# gerbalino0_3_1.net
KiCad netlist of a schematic drawn in EAGLE
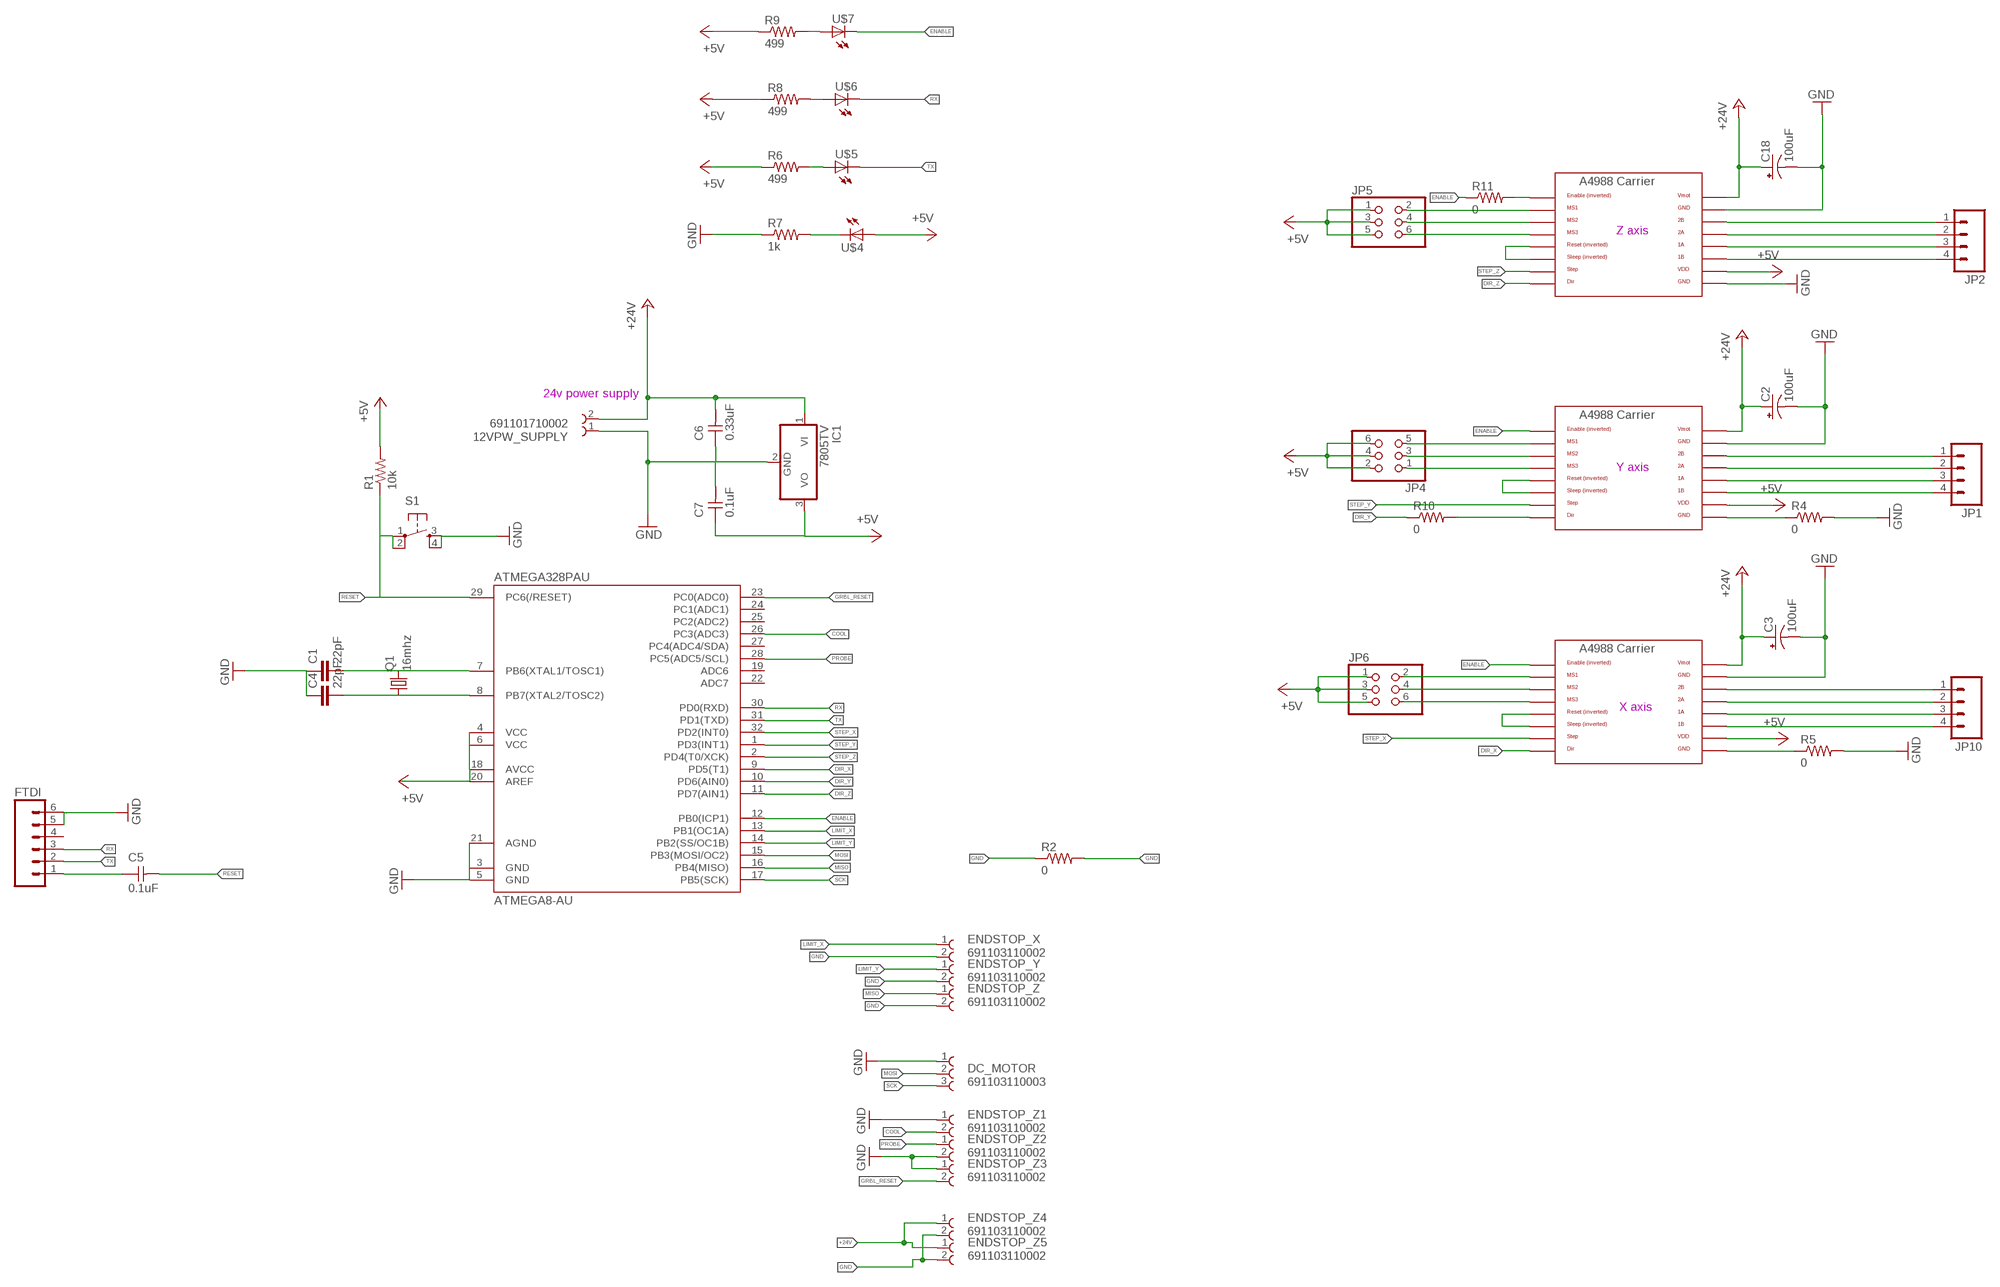
[diagram p0: schematic, sheet 1]

(export (version "E")
  (design (tool "Eeschema 10.0.6"))
  (components
    (comp (ref "12VPW_SUPPLY")
      (value "691101710002")
      (footprint "eagle-import:691101710002")
      (libsource (lib "eagle-import") (part "691101710002"))
    )
    (comp (ref "ATMEGA328PAU")
      (value "ATMEGA8-AU")
      (footprint "eagle-import:TQFP32-08")
      (libsource (lib "eagle-import") (part "ATMEGA8-AU"))
    )
    (comp (ref "C1")
      (value "22pF")
      (footprint "eagle-import:1206")
      (libsource (lib "eagle-import") (part "CAP1206"))
    )
    (comp (ref "C2")
      (value "100uF")
      (footprint "eagle-import:UD-10X10_NICHICON")
      (libsource (lib "eagle-import") (part "CPOL-USUD-10X10"))
    )
    (comp (ref "C3")
      (value "100uF")
      (footprint "eagle-import:UD-10X10_NICHICON")
      (libsource (lib "eagle-import") (part "CPOL-USUD-10X10"))
    )
    (comp (ref "C4")
      (value "22pF")
      (footprint "eagle-import:1206")
      (libsource (lib "eagle-import") (part "CAP1206"))
    )
    (comp (ref "C5")
      (value "0.1uF")
      (footprint "eagle-import:1206")
      (libsource (lib "eagle-import") (part "UNPOLARIZED_CAPACITOR1206"))
    )
    (comp (ref "C6")
      (value "0.33uF")
      (footprint "eagle-import:1206")
      (libsource (lib "eagle-import") (part "UNPOLARIZED_CAPACITOR1206"))
    )
    (comp (ref "C7")
      (value "0.1uF")
      (footprint "eagle-import:1206")
      (libsource (lib "eagle-import") (part "UNPOLARIZED_CAPACITOR1206"))
    )
    (comp (ref "C18")
      (value "100uF")
      (footprint "eagle-import:UD-10X10_NICHICON")
      (libsource (lib "eagle-import") (part "CPOL-USUD-10X10"))
    )
    (comp (ref "DC_MOTOR")
      (value "691103110003")
      (footprint "eagle-import:691103110003")
      (libsource (lib "eagle-import") (part "691103110003"))
    )
    (comp (ref "ENDSTOP_X")
      (value "691103110002")
      (footprint "eagle-import:691103110002")
      (libsource (lib "eagle-import") (part "691103110002"))
    )
    (comp (ref "ENDSTOP_Y")
      (value "691103110002")
      (footprint "eagle-import:691103110002")
      (libsource (lib "eagle-import") (part "691103110002"))
    )
    (comp (ref "ENDSTOP_Z")
      (value "691103110002")
      (footprint "eagle-import:691103110002")
      (libsource (lib "eagle-import") (part "691103110002"))
    )
    (comp (ref "ENDSTOP_Z1")
      (value "691103110002")
      (footprint "eagle-import:691103110002")
      (libsource (lib "eagle-import") (part "691103110002"))
    )
    (comp (ref "ENDSTOP_Z2")
      (value "691103110002")
      (footprint "eagle-import:691103110002")
      (libsource (lib "eagle-import") (part "691103110002"))
    )
    (comp (ref "ENDSTOP_Z3")
      (value "691103110002")
      (footprint "eagle-import:691103110002")
      (libsource (lib "eagle-import") (part "691103110002"))
    )
    (comp (ref "ENDSTOP_Z4")
      (value "691103110002")
      (footprint "eagle-import:691103110002")
      (libsource (lib "eagle-import") (part "691103110002"))
    )
    (comp (ref "ENDSTOP_Z5")
      (value "691103110002")
      (footprint "eagle-import:691103110002")
      (libsource (lib "eagle-import") (part "691103110002"))
    )
    (comp (ref "FTDI")
      (value "M06SMD")
      (footprint "eagle-import:1X06-SMD")
      (libsource (lib "eagle-import") (part "M06SMD"))
    )
    (comp (ref "IC1")
      (value "7805TV")
      (footprint "eagle-import:TO220V")
      (libsource (lib "eagle-import") (part "78TV05"))
    )
    (comp (ref "JP1")
      (value "M04LONGPADS")
      (footprint "eagle-import:1X04_LONGPADS")
      (libsource (lib "eagle-import") (part "M04LONGPADS"))
    )
    (comp (ref "JP2")
      (value "M04LONGPADS")
      (footprint "eagle-import:1X04_LONGPADS")
      (libsource (lib "eagle-import") (part "M04LONGPADS"))
    )
    (comp (ref "JP4")
      (value "PINHD-2X3-SMD")
      (footprint "eagle-import:2X03SMD")
      (libsource (lib "eagle-import") (part "PINHD-2X3-SMD"))
    )
    (comp (ref "JP5")
      (value "PINHD-2X3-SMD")
      (footprint "eagle-import:2X03SMD")
      (libsource (lib "eagle-import") (part "PINHD-2X3-SMD"))
    )
    (comp (ref "JP6")
      (value "PINHD-2X3-SMD")
      (footprint "eagle-import:2X03SMD")
      (libsource (lib "eagle-import") (part "PINHD-2X3-SMD"))
    )
    (comp (ref "JP10")
      (value "M04LONGPADS")
      (footprint "eagle-import:1X04_LONGPADS")
      (libsource (lib "eagle-import") (part "M04LONGPADS"))
    )
    (comp (ref "Q1")
      (value "16mhz")
      (footprint "eagle-import:CSM-7X-DU")
      (libsource (lib "eagle-import") (part "CSM-7X-DU"))
    )
    (comp (ref "R1")
      (value "10k")
      (footprint "eagle-import:1206")
      (libsource (lib "eagle-import") (part "01_SparkFun_RESISTOR1206"))
    )
    (comp (ref "R2")
      (value "0")
      (footprint "eagle-import:1206")
      (libsource (lib "eagle-import") (part "01_SparkFun_RESISTOR1206"))
    )
    (comp (ref "R4")
      (value "0")
      (footprint "eagle-import:1206")
      (libsource (lib "eagle-import") (part "01_SparkFun_RESISTOR1206"))
    )
    (comp (ref "R5")
      (value "0")
      (footprint "eagle-import:1206")
      (libsource (lib "eagle-import") (part "01_SparkFun_RESISTOR1206"))
    )
    (comp (ref "R6")
      (value "499")
      (footprint "eagle-import:1206")
      (libsource (lib "eagle-import") (part "RESISTOR1206"))
    )
    (comp (ref "R7")
      (value "1k")
      (footprint "eagle-import:1206")
      (libsource (lib "eagle-import") (part "RESISTOR1206"))
    )
    (comp (ref "R8")
      (value "499")
      (footprint "eagle-import:1206")
      (libsource (lib "eagle-import") (part "RESISTOR1206"))
    )
    (comp (ref "R9")
      (value "499")
      (footprint "eagle-import:1206")
      (libsource (lib "eagle-import") (part "RESISTOR1206"))
    )
    (comp (ref "R10")
      (value "0")
      (footprint "eagle-import:1206")
      (libsource (lib "eagle-import") (part "01_SparkFun_RESISTOR1206"))
    )
    (comp (ref "R11")
      (value "0")
      (footprint "eagle-import:1206")
      (libsource (lib "eagle-import") (part "01_SparkFun_RESISTOR1206"))
    )
    (comp (ref "S1")
      (value "6MM_SWITCH6MM_SWITCH")
      (footprint "eagle-import:6MM_SWITCH")
      (libsource (lib "eagle-import") (part "6MM_SWITCH6MM_SWITCH"))
    )
    (comp (ref "U$1")
      (value "POLOLU_A4983CARRIER")
      (footprint "eagle-import:A4988BREAKOUT")
      (libsource (lib "eagle-import") (part "POLOLU_A4983CARRIER"))
    )
    (comp (ref "U$2")
      (value "POLOLU_A4983CARRIER")
      (footprint "eagle-import:A4988BREAKOUT")
      (libsource (lib "eagle-import") (part "POLOLU_A4983CARRIER"))
    )
    (comp (ref "U$3")
      (value "POLOLU_A4983CARRIER")
      (footprint "eagle-import:A4988BREAKOUT")
      (libsource (lib "eagle-import") (part "POLOLU_A4983CARRIER"))
    )
    (comp (ref "U$4")
      (value "LED1206")
      (footprint "eagle-import:1206")
      (libsource (lib "eagle-import") (part "LED1206"))
    )
    (comp (ref "U$5")
      (value "LED1206")
      (footprint "eagle-import:1206")
      (libsource (lib "eagle-import") (part "LED1206"))
    )
    (comp (ref "U$6")
      (value "LED1206")
      (footprint "eagle-import:1206")
      (libsource (lib "eagle-import") (part "LED1206"))
    )
    (comp (ref "U$7")
      (value "LED1206")
      (footprint "eagle-import:1206")
      (libsource (lib "eagle-import") (part "LED1206"))
    )
  )
  (nets
    (net (code "1") (name "+5V") (class "Default")
      (node (ref "ATMEGA328PAU") (pin "18") (pinfunction "AVCC_18") (pintype "passive"))
      (node (ref "ATMEGA328PAU") (pin "20") (pinfunction "AREF_20") (pintype "passive"))
      (node (ref "ATMEGA328PAU") (pin "4") (pinfunction "VCC_4") (pintype "power_in"))
      (node (ref "ATMEGA328PAU") (pin "6") (pinfunction "VCC_6") (pintype "power_in"))
      (node (ref "C7") (pin "1") (pinfunction "1_1") (pintype "passive"))
      (node (ref "IC1") (pin "3") (pinfunction "VO_3") (pintype "passive"))
      (node (ref "JP4") (pin "2") (pinfunction "2_2") (pintype "passive"))
      (node (ref "JP4") (pin "4") (pinfunction "4_4") (pintype "passive"))
      (node (ref "JP4") (pin "6") (pinfunction "6_6") (pintype "passive"))
      (node (ref "JP5") (pin "1") (pinfunction "1_1") (pintype "passive"))
      (node (ref "JP5") (pin "3") (pinfunction "3_3") (pintype "passive"))
      (node (ref "JP5") (pin "5") (pinfunction "5_5") (pintype "passive"))
      (node (ref "JP6") (pin "1") (pinfunction "1_1") (pintype "passive"))
      (node (ref "JP6") (pin "3") (pinfunction "3_3") (pintype "passive"))
      (node (ref "JP6") (pin "5") (pinfunction "5_5") (pintype "passive"))
      (node (ref "R1") (pin "2") (pinfunction "2_2") (pintype "passive"))
      (node (ref "R6") (pin "1") (pinfunction "1_1") (pintype "passive"))
      (node (ref "R8") (pin "1") (pinfunction "1_1") (pintype "passive"))
      (node (ref "R9") (pin "1") (pinfunction "1_1") (pintype "passive"))
      (node (ref "U$1") (pin "VDD") (pinfunction "VDD_VDD") (pintype "power_in"))
      (node (ref "U$2") (pin "VDD") (pinfunction "VDD_VDD") (pintype "power_in"))
      (node (ref "U$3") (pin "VDD") (pinfunction "VDD_VDD") (pintype "power_in"))
      (node (ref "U$4") (pin "1") (pinfunction "A_1") (pintype "passive"))
    )
    (net (code "2") (name "+24V") (class "Default")
      (node (ref "12VPW_SUPPLY") (pin "2") (pinfunction "2_2") (pintype "passive"))
      (node (ref "C18") (pin "+") (pinfunction "+_+") (pintype "passive"))
      (node (ref "C2") (pin "+") (pinfunction "+_+") (pintype "passive"))
      (node (ref "C3") (pin "+") (pinfunction "+_+") (pintype "passive"))
      (node (ref "C6") (pin "2") (pinfunction "2_2") (pintype "passive"))
      (node (ref "ENDSTOP_Z4") (pin "1") (pinfunction "1_1") (pintype "passive"))
      (node (ref "ENDSTOP_Z5") (pin "1") (pinfunction "1_1") (pintype "passive"))
      (node (ref "IC1") (pin "1") (pinfunction "VI_1") (pintype "input"))
      (node (ref "U$1") (pin "VMOT") (pinfunction "VMOT_VMOT") (pintype "power_in"))
      (node (ref "U$2") (pin "VMOT") (pinfunction "VMOT_VMOT") (pintype "power_in"))
      (node (ref "U$3") (pin "VMOT") (pinfunction "VMOT_VMOT") (pintype "power_in"))
    )
    (net (code "3") (name "COOL") (class "Default")
      (node (ref "ATMEGA328PAU") (pin "26") (pinfunction "PC3(ADC3)_26") (pintype "bidirectional"))
      (node (ref "ENDSTOP_Z1") (pin "2") (pinfunction "2_2") (pintype "passive"))
    )
    (net (code "4") (name "DIR_X") (class "Default")
      (node (ref "ATMEGA328PAU") (pin "9") (pinfunction "PD5(T1)_9") (pintype "bidirectional"))
      (node (ref "U$3") (pin "DIR") (pinfunction "DIR_DIR") (pintype "input"))
    )
    (net (code "5") (name "DIR_Y") (class "Default")
      (node (ref "ATMEGA328PAU") (pin "10") (pinfunction "PD6(AIN0)_10") (pintype "bidirectional"))
      (node (ref "R10") (pin "1") (pinfunction "1_1") (pintype "passive"))
    )
    (net (code "6") (name "DIR_Z") (class "Default")
      (node (ref "ATMEGA328PAU") (pin "11") (pinfunction "PD7(AIN1)_11") (pintype "bidirectional"))
      (node (ref "U$2") (pin "DIR") (pinfunction "DIR_DIR") (pintype "input"))
    )
    (net (code "7") (name "ENABLE") (class "Default")
      (node (ref "ATMEGA328PAU") (pin "12") (pinfunction "PB0(ICP1)_12") (pintype "bidirectional"))
      (node (ref "R11") (pin "1") (pinfunction "1_1") (pintype "passive"))
      (node (ref "R11") (pin "2") (pinfunction "2_2") (pintype "passive"))
      (node (ref "U$1") (pin "EN") (pinfunction "EN_EN") (pintype "input"))
      (node (ref "U$2") (pin "EN") (pinfunction "EN_EN") (pintype "input"))
      (node (ref "U$3") (pin "EN") (pinfunction "EN_EN") (pintype "input"))
      (node (ref "U$7") (pin "2") (pinfunction "C_2") (pintype "passive"))
    )
    (net (code "8") (name "GND") (class "Default")
      (node (ref "12VPW_SUPPLY") (pin "1") (pinfunction "1_1") (pintype "passive"))
      (node (ref "ATMEGA328PAU") (pin "21") (pinfunction "AGND_21") (pintype "power_in"))
      (node (ref "ATMEGA328PAU") (pin "3") (pinfunction "GND_3") (pintype "power_in"))
      (node (ref "ATMEGA328PAU") (pin "5") (pinfunction "GND_5") (pintype "power_in"))
      (node (ref "C1") (pin "1") (pinfunction "1_1") (pintype "passive"))
      (node (ref "C18") (pin "-") (pinfunction "-_-") (pintype "passive"))
      (node (ref "C2") (pin "-") (pinfunction "-_-") (pintype "passive"))
      (node (ref "C3") (pin "-") (pinfunction "-_-") (pintype "passive"))
      (node (ref "C4") (pin "1") (pinfunction "1_1") (pintype "passive"))
      (node (ref "C6") (pin "1") (pinfunction "1_1") (pintype "passive"))
      (node (ref "C7") (pin "2") (pinfunction "2_2") (pintype "passive"))
      (node (ref "DC_MOTOR") (pin "1") (pinfunction "1_1") (pintype "passive"))
      (node (ref "ENDSTOP_X") (pin "2") (pinfunction "2_2") (pintype "passive"))
      (node (ref "ENDSTOP_Y") (pin "2") (pinfunction "2_2") (pintype "passive"))
      (node (ref "ENDSTOP_Z") (pin "2") (pinfunction "2_2") (pintype "passive"))
      (node (ref "ENDSTOP_Z1") (pin "1") (pinfunction "1_1") (pintype "passive"))
      (node (ref "ENDSTOP_Z2") (pin "2") (pinfunction "2_2") (pintype "passive"))
      (node (ref "ENDSTOP_Z3") (pin "1") (pinfunction "1_1") (pintype "passive"))
      (node (ref "ENDSTOP_Z4") (pin "2") (pinfunction "2_2") (pintype "passive"))
      (node (ref "ENDSTOP_Z5") (pin "2") (pinfunction "2_2") (pintype "passive"))
      (node (ref "FTDI") (pin "5") (pinfunction "5_5") (pintype "passive"))
      (node (ref "FTDI") (pin "6") (pinfunction "6_6") (pintype "passive"))
      (node (ref "IC1") (pin "2") (pinfunction "GND_2") (pintype "passive"))
      (node (ref "R2") (pin "1") (pinfunction "1_1") (pintype "passive"))
      (node (ref "R2") (pin "2") (pinfunction "2_2") (pintype "passive"))
      (node (ref "R4") (pin "1") (pinfunction "1_1") (pintype "passive"))
      (node (ref "R4") (pin "2") (pinfunction "2_2") (pintype "passive"))
      (node (ref "R5") (pin "1") (pinfunction "1_1") (pintype "passive"))
      (node (ref "R5") (pin "2") (pinfunction "2_2") (pintype "passive"))
      (node (ref "R7") (pin "1") (pinfunction "1_1") (pintype "passive"))
      (node (ref "S1") (pin "3") (pinfunction "S_3") (pintype "passive"))
      (node (ref "S1") (pin "4") (pinfunction "S1_4") (pintype "passive"))
      (node (ref "U$1") (pin "GND") (pinfunction "GND_GND") (pintype "power_in"))
      (node (ref "U$1") (pin "GND@0") (pinfunction "GND_GND@0") (pintype "power_in"))
      (node (ref "U$2") (pin "GND") (pinfunction "GND_GND") (pintype "power_in"))
      (node (ref "U$2") (pin "GND@0") (pinfunction "GND_GND@0") (pintype "power_in"))
      (node (ref "U$3") (pin "GND") (pinfunction "GND_GND") (pintype "power_in"))
      (node (ref "U$3") (pin "GND@0") (pinfunction "GND_GND@0") (pintype "power_in"))
    )
    (net (code "9") (name "GRBL_RESET") (class "Default")
      (node (ref "ATMEGA328PAU") (pin "23") (pinfunction "PC0(ADC0)_23") (pintype "bidirectional"))
      (node (ref "ENDSTOP_Z3") (pin "2") (pinfunction "2_2") (pintype "passive"))
    )
    (net (code "10") (name "LIMIT_X") (class "Default")
      (node (ref "ATMEGA328PAU") (pin "13") (pinfunction "PB1(OC1A)_13") (pintype "bidirectional"))
      (node (ref "ENDSTOP_X") (pin "1") (pinfunction "1_1") (pintype "passive"))
    )
    (net (code "11") (name "LIMIT_Y") (class "Default")
      (node (ref "ATMEGA328PAU") (pin "14") (pinfunction "PB2(SS/OC1B)_14") (pintype "bidirectional"))
      (node (ref "ENDSTOP_Y") (pin "1") (pinfunction "1_1") (pintype "passive"))
    )
    (net (code "12") (name "MISO") (class "Default")
      (node (ref "ATMEGA328PAU") (pin "16") (pinfunction "PB4(MISO)_16") (pintype "bidirectional"))
      (node (ref "ENDSTOP_Z") (pin "1") (pinfunction "1_1") (pintype "passive"))
    )
    (net (code "13") (name "MOSI") (class "Default")
      (node (ref "ATMEGA328PAU") (pin "15") (pinfunction "PB3(MOSI/OC2)_15") (pintype "bidirectional"))
      (node (ref "DC_MOTOR") (pin "2") (pinfunction "2_2") (pintype "passive"))
    )
    (net (code "14") (name "Net-(ATMEGA328PAU-PB6(XTAL1{slash}TOSC1))") (class "Default")
      (node (ref "ATMEGA328PAU") (pin "7") (pinfunction "PB6(XTAL1/TOSC1)_7") (pintype "bidirectional"))
      (node (ref "C1") (pin "2") (pinfunction "2_2") (pintype "passive"))
      (node (ref "Q1") (pin "2") (pinfunction "2_2") (pintype "passive"))
    )
    (net (code "15") (name "Net-(ATMEGA328PAU-PB7(XTAL2{slash}TOSC2))") (class "Default")
      (node (ref "ATMEGA328PAU") (pin "8") (pinfunction "PB7(XTAL2/TOSC2)_8") (pintype "bidirectional"))
      (node (ref "C4") (pin "2") (pinfunction "2_2") (pintype "passive"))
      (node (ref "Q1") (pin "1") (pinfunction "1_1") (pintype "passive"))
    )
    (net (code "16") (name "Net-(C5-Pad1)") (class "Default")
      (node (ref "C5") (pin "1") (pinfunction "1_1") (pintype "passive"))
      (node (ref "FTDI") (pin "1") (pinfunction "1_1") (pintype "passive"))
    )
    (net (code "17") (name "Net-(JP1-Pad1)") (class "Default")
      (node (ref "JP1") (pin "1") (pinfunction "1_1") (pintype "passive"))
      (node (ref "U$1") (pin "2B") (pinfunction "2B_2B") (pintype "output"))
    )
    (net (code "18") (name "Net-(JP1-Pad2)") (class "Default")
      (node (ref "JP1") (pin "2") (pinfunction "2_2") (pintype "passive"))
      (node (ref "U$1") (pin "2A") (pinfunction "2A_2A") (pintype "output"))
    )
    (net (code "19") (name "Net-(JP1-Pad3)") (class "Default")
      (node (ref "JP1") (pin "3") (pinfunction "3_3") (pintype "passive"))
      (node (ref "U$1") (pin "1A") (pinfunction "1A_1A") (pintype "output"))
    )
    (net (code "20") (name "Net-(JP1-Pad4)") (class "Default")
      (node (ref "JP1") (pin "4") (pinfunction "4_4") (pintype "passive"))
      (node (ref "U$1") (pin "1B") (pinfunction "1B_1B") (pintype "output"))
    )
    (net (code "21") (name "Net-(JP2-Pad1)") (class "Default")
      (node (ref "JP2") (pin "1") (pinfunction "1_1") (pintype "passive"))
      (node (ref "U$2") (pin "2B") (pinfunction "2B_2B") (pintype "output"))
    )
    (net (code "22") (name "Net-(JP2-Pad2)") (class "Default")
      (node (ref "JP2") (pin "2") (pinfunction "2_2") (pintype "passive"))
      (node (ref "U$2") (pin "2A") (pinfunction "2A_2A") (pintype "output"))
    )
    (net (code "23") (name "Net-(JP2-Pad3)") (class "Default")
      (node (ref "JP2") (pin "3") (pinfunction "3_3") (pintype "passive"))
      (node (ref "U$2") (pin "1A") (pinfunction "1A_1A") (pintype "output"))
    )
    (net (code "24") (name "Net-(JP2-Pad4)") (class "Default")
      (node (ref "JP2") (pin "4") (pinfunction "4_4") (pintype "passive"))
      (node (ref "U$2") (pin "1B") (pinfunction "1B_1B") (pintype "output"))
    )
    (net (code "25") (name "Net-(JP4-Pad1)") (class "Default")
      (node (ref "JP4") (pin "1") (pinfunction "1_1") (pintype "passive"))
      (node (ref "U$1") (pin "MS3") (pinfunction "MS3_MS3") (pintype "input"))
    )
    (net (code "26") (name "Net-(JP4-Pad3)") (class "Default")
      (node (ref "JP4") (pin "3") (pinfunction "3_3") (pintype "passive"))
      (node (ref "U$1") (pin "MS2") (pinfunction "MS2_MS2") (pintype "input"))
    )
    (net (code "27") (name "Net-(JP4-Pad5)") (class "Default")
      (node (ref "JP4") (pin "5") (pinfunction "5_5") (pintype "passive"))
      (node (ref "U$1") (pin "MS1") (pinfunction "MS1_MS1") (pintype "input"))
    )
    (net (code "28") (name "Net-(JP5-Pad2)") (class "Default")
      (node (ref "JP5") (pin "2") (pinfunction "2_2") (pintype "passive"))
      (node (ref "U$2") (pin "MS1") (pinfunction "MS1_MS1") (pintype "input"))
    )
    (net (code "29") (name "Net-(JP5-Pad4)") (class "Default")
      (node (ref "JP5") (pin "4") (pinfunction "4_4") (pintype "passive"))
      (node (ref "U$2") (pin "MS2") (pinfunction "MS2_MS2") (pintype "input"))
    )
    (net (code "30") (name "Net-(JP5-Pad6)") (class "Default")
      (node (ref "JP5") (pin "6") (pinfunction "6_6") (pintype "passive"))
      (node (ref "U$2") (pin "MS3") (pinfunction "MS3_MS3") (pintype "input"))
    )
    (net (code "31") (name "Net-(JP6-Pad2)") (class "Default")
      (node (ref "JP6") (pin "2") (pinfunction "2_2") (pintype "passive"))
      (node (ref "U$3") (pin "MS1") (pinfunction "MS1_MS1") (pintype "input"))
    )
    (net (code "32") (name "Net-(JP6-Pad4)") (class "Default")
      (node (ref "JP6") (pin "4") (pinfunction "4_4") (pintype "passive"))
      (node (ref "U$3") (pin "MS2") (pinfunction "MS2_MS2") (pintype "input"))
    )
    (net (code "33") (name "Net-(JP6-Pad6)") (class "Default")
      (node (ref "JP6") (pin "6") (pinfunction "6_6") (pintype "passive"))
      (node (ref "U$3") (pin "MS3") (pinfunction "MS3_MS3") (pintype "input"))
    )
    (net (code "34") (name "Net-(JP10-Pad1)") (class "Default")
      (node (ref "JP10") (pin "1") (pinfunction "1_1") (pintype "passive"))
      (node (ref "U$3") (pin "2B") (pinfunction "2B_2B") (pintype "output"))
    )
    (net (code "35") (name "Net-(JP10-Pad2)") (class "Default")
      (node (ref "JP10") (pin "2") (pinfunction "2_2") (pintype "passive"))
      (node (ref "U$3") (pin "2A") (pinfunction "2A_2A") (pintype "output"))
    )
    (net (code "36") (name "Net-(JP10-Pad3)") (class "Default")
      (node (ref "JP10") (pin "3") (pinfunction "3_3") (pintype "passive"))
      (node (ref "U$3") (pin "1A") (pinfunction "1A_1A") (pintype "output"))
    )
    (net (code "37") (name "Net-(JP10-Pad4)") (class "Default")
      (node (ref "JP10") (pin "4") (pinfunction "4_4") (pintype "passive"))
      (node (ref "U$3") (pin "1B") (pinfunction "1B_1B") (pintype "output"))
    )
    (net (code "38") (name "Net-(R10-Pad2)") (class "Default")
      (node (ref "R10") (pin "2") (pinfunction "2_2") (pintype "passive"))
      (node (ref "U$1") (pin "DIR") (pinfunction "DIR_DIR") (pintype "input"))
    )
    (net (code "39") (name "Net-(U$1-SLEEP)") (class "Default")
      (node (ref "U$1") (pin "RST") (pinfunction "RST_RST") (pintype "input"))
      (node (ref "U$1") (pin "SLP") (pinfunction "SLEEP_SLP") (pintype "input"))
    )
    (net (code "40") (name "Net-(U$2-SLEEP)") (class "Default")
      (node (ref "U$2") (pin "RST") (pinfunction "RST_RST") (pintype "input"))
      (node (ref "U$2") (pin "SLP") (pinfunction "SLEEP_SLP") (pintype "input"))
    )
    (net (code "41") (name "Net-(U$3-SLEEP)") (class "Default")
      (node (ref "U$3") (pin "RST") (pinfunction "RST_RST") (pintype "input"))
      (node (ref "U$3") (pin "SLP") (pinfunction "SLEEP_SLP") (pintype "input"))
    )
    (net (code "42") (name "Net-(U$4-C)") (class "Default")
      (node (ref "R7") (pin "2") (pinfunction "2_2") (pintype "passive"))
      (node (ref "U$4") (pin "2") (pinfunction "C_2") (pintype "passive"))
    )
    (net (code "43") (name "Net-(U$5-A)") (class "Default")
      (node (ref "R6") (pin "2") (pinfunction "2_2") (pintype "passive"))
      (node (ref "U$5") (pin "1") (pinfunction "A_1") (pintype "passive"))
    )
    (net (code "44") (name "Net-(U$6-A)") (class "Default")
      (node (ref "R8") (pin "2") (pinfunction "2_2") (pintype "passive"))
      (node (ref "U$6") (pin "1") (pinfunction "A_1") (pintype "passive"))
    )
    (net (code "45") (name "Net-(U$7-A)") (class "Default")
      (node (ref "R9") (pin "2") (pinfunction "2_2") (pintype "passive"))
      (node (ref "U$7") (pin "1") (pinfunction "A_1") (pintype "passive"))
    )
    (net (code "46") (name "PROBE") (class "Default")
      (node (ref "ATMEGA328PAU") (pin "28") (pinfunction "PC5(ADC5/SCL)_28") (pintype "bidirectional"))
      (node (ref "ENDSTOP_Z2") (pin "1") (pinfunction "1_1") (pintype "passive"))
    )
    (net (code "47") (name "RESET") (class "Default")
      (node (ref "ATMEGA328PAU") (pin "29") (pinfunction "PC6(/RESET)_29") (pintype "bidirectional"))
      (node (ref "C5") (pin "2") (pinfunction "2_2") (pintype "passive"))
      (node (ref "R1") (pin "1") (pinfunction "1_1") (pintype "passive"))
      (node (ref "S1") (pin "1") (pinfunction "P_1") (pintype "passive"))
      (node (ref "S1") (pin "2") (pinfunction "P1_2") (pintype "passive"))
    )
    (net (code "48") (name "RX") (class "Default")
      (node (ref "ATMEGA328PAU") (pin "30") (pinfunction "PD0(RXD)_30") (pintype "bidirectional"))
      (node (ref "FTDI") (pin "3") (pinfunction "3_3") (pintype "passive"))
      (node (ref "U$6") (pin "2") (pinfunction "C_2") (pintype "passive"))
    )
    (net (code "49") (name "SCK") (class "Default")
      (node (ref "ATMEGA328PAU") (pin "17") (pinfunction "PB5(SCK)_17") (pintype "bidirectional"))
      (node (ref "DC_MOTOR") (pin "3") (pinfunction "3_3") (pintype "passive"))
    )
    (net (code "50") (name "STEP_X") (class "Default")
      (node (ref "ATMEGA328PAU") (pin "32") (pinfunction "PD2(INT0)_32") (pintype "bidirectional"))
      (node (ref "U$3") (pin "STEP") (pinfunction "STEP_STEP") (pintype "input"))
    )
    (net (code "51") (name "STEP_Y") (class "Default")
      (node (ref "ATMEGA328PAU") (pin "1") (pinfunction "PD3(INT1)_1") (pintype "bidirectional"))
      (node (ref "U$1") (pin "STEP") (pinfunction "STEP_STEP") (pintype "input"))
    )
    (net (code "52") (name "STEP_Z") (class "Default")
      (node (ref "ATMEGA328PAU") (pin "2") (pinfunction "PD4(T0/XCK)_2") (pintype "bidirectional"))
      (node (ref "U$2") (pin "STEP") (pinfunction "STEP_STEP") (pintype "input"))
    )
    (net (code "53") (name "TX") (class "Default")
      (node (ref "ATMEGA328PAU") (pin "31") (pinfunction "PD1(TXD)_31") (pintype "bidirectional"))
      (node (ref "FTDI") (pin "2") (pinfunction "2_2") (pintype "passive"))
      (node (ref "U$5") (pin "2") (pinfunction "C_2") (pintype "passive"))
    )
    (net (code "54") (name "unconnected-(ATMEGA328PAU-ADC6-Pad19)") (class "Default")
      (node (ref "ATMEGA328PAU") (pin "19") (pinfunction "ADC6_19") (pintype "passive"))
    )
    (net (code "55") (name "unconnected-(ATMEGA328PAU-ADC7-Pad22)") (class "Default")
      (node (ref "ATMEGA328PAU") (pin "22") (pinfunction "ADC7_22") (pintype "passive"))
    )
    (net (code "56") (name "unconnected-(ATMEGA328PAU-PC1(ADC1)-Pad24)") (class "Default")
      (node (ref "ATMEGA328PAU") (pin "24") (pinfunction "PC1(ADC1)_24") (pintype "bidirectional"))
    )
    (net (code "57") (name "unconnected-(ATMEGA328PAU-PC2(ADC2)-Pad25)") (class "Default")
      (node (ref "ATMEGA328PAU") (pin "25") (pinfunction "PC2(ADC2)_25") (pintype "bidirectional"))
    )
    (net (code "58") (name "unconnected-(ATMEGA328PAU-PC4(ADC4{slash}SDA)-Pad27)") (class "Default")
      (node (ref "ATMEGA328PAU") (pin "27") (pinfunction "PC4(ADC4/SDA)_27") (pintype "bidirectional"))
    )
    (net (code "59") (name "unconnected-(FTDI-Pad4)") (class "Default")
      (node (ref "FTDI") (pin "4") (pinfunction "4_4") (pintype "passive"))
    )
  )
)
